# buttons_v2.net
KiCad netlist of a schematic drawn in EAGLE
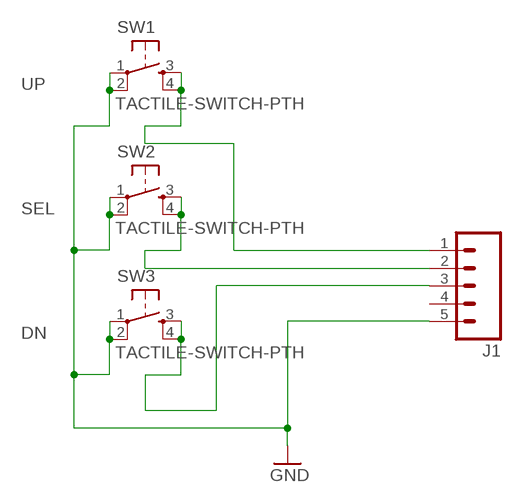
[diagram p0: schematic, sheet 1]

(export (version "E")
  (design (tool "Eeschema 10.0.6"))
  (components
    (comp (ref "J1")
      (value "M05PTH")
      (footprint "eagle-import:1X05")
      (libsource (lib "eagle-import") (part "M05PTH"))
    )
    (comp (ref "SW1")
      (value "TACTILE-SWITCH-PTH")
      (footprint "eagle-import:TAC-SWITCH-PTH")
      (libsource (lib "eagle-import") (part "TACTILE-SWITCH-PTH"))
    )
    (comp (ref "SW2")
      (value "TACTILE-SWITCH-PTH")
      (footprint "eagle-import:TAC-SWITCH-PTH")
      (libsource (lib "eagle-import") (part "TACTILE-SWITCH-PTH"))
    )
    (comp (ref "SW3")
      (value "TACTILE-SWITCH-PTH")
      (footprint "eagle-import:TAC-SWITCH-PTH")
      (libsource (lib "eagle-import") (part "TACTILE-SWITCH-PTH"))
    )
  )
  (nets
    (net (code "1") (name "GND") (class "Default")
      (node (ref "J1") (pin "5") (pinfunction "5_5") (pintype "passive"))
      (node (ref "SW1") (pin "1") (pinfunction "1_1") (pintype "passive"))
      (node (ref "SW1") (pin "2") (pinfunction "2_2") (pintype "passive"))
      (node (ref "SW2") (pin "1") (pinfunction "1_1") (pintype "passive"))
      (node (ref "SW2") (pin "2") (pinfunction "2_2") (pintype "passive"))
      (node (ref "SW3") (pin "1") (pinfunction "1_1") (pintype "passive"))
      (node (ref "SW3") (pin "2") (pinfunction "2_2") (pintype "passive"))
    )
    (net (code "2") (name "Net-(J1-Pad1)") (class "Default")
      (node (ref "J1") (pin "1") (pinfunction "1_1") (pintype "passive"))
      (node (ref "SW1") (pin "3") (pinfunction "3_3") (pintype "passive"))
      (node (ref "SW1") (pin "4") (pinfunction "4_4") (pintype "passive"))
    )
    (net (code "3") (name "Net-(J1-Pad2)") (class "Default")
      (node (ref "J1") (pin "2") (pinfunction "2_2") (pintype "passive"))
      (node (ref "SW2") (pin "3") (pinfunction "3_3") (pintype "passive"))
      (node (ref "SW2") (pin "4") (pinfunction "4_4") (pintype "passive"))
    )
    (net (code "4") (name "Net-(J1-Pad3)") (class "Default")
      (node (ref "J1") (pin "3") (pinfunction "3_3") (pintype "passive"))
      (node (ref "SW3") (pin "3") (pinfunction "3_3") (pintype "passive"))
      (node (ref "SW3") (pin "4") (pinfunction "4_4") (pintype "passive"))
    )
    (net (code "5") (name "unconnected-(J1-Pad4)") (class "Default")
      (node (ref "J1") (pin "4") (pinfunction "4_4") (pintype "passive"))
    )
  )
)
